# BattPower.net
KiCad netlist of a schematic drawn in Altium Designer
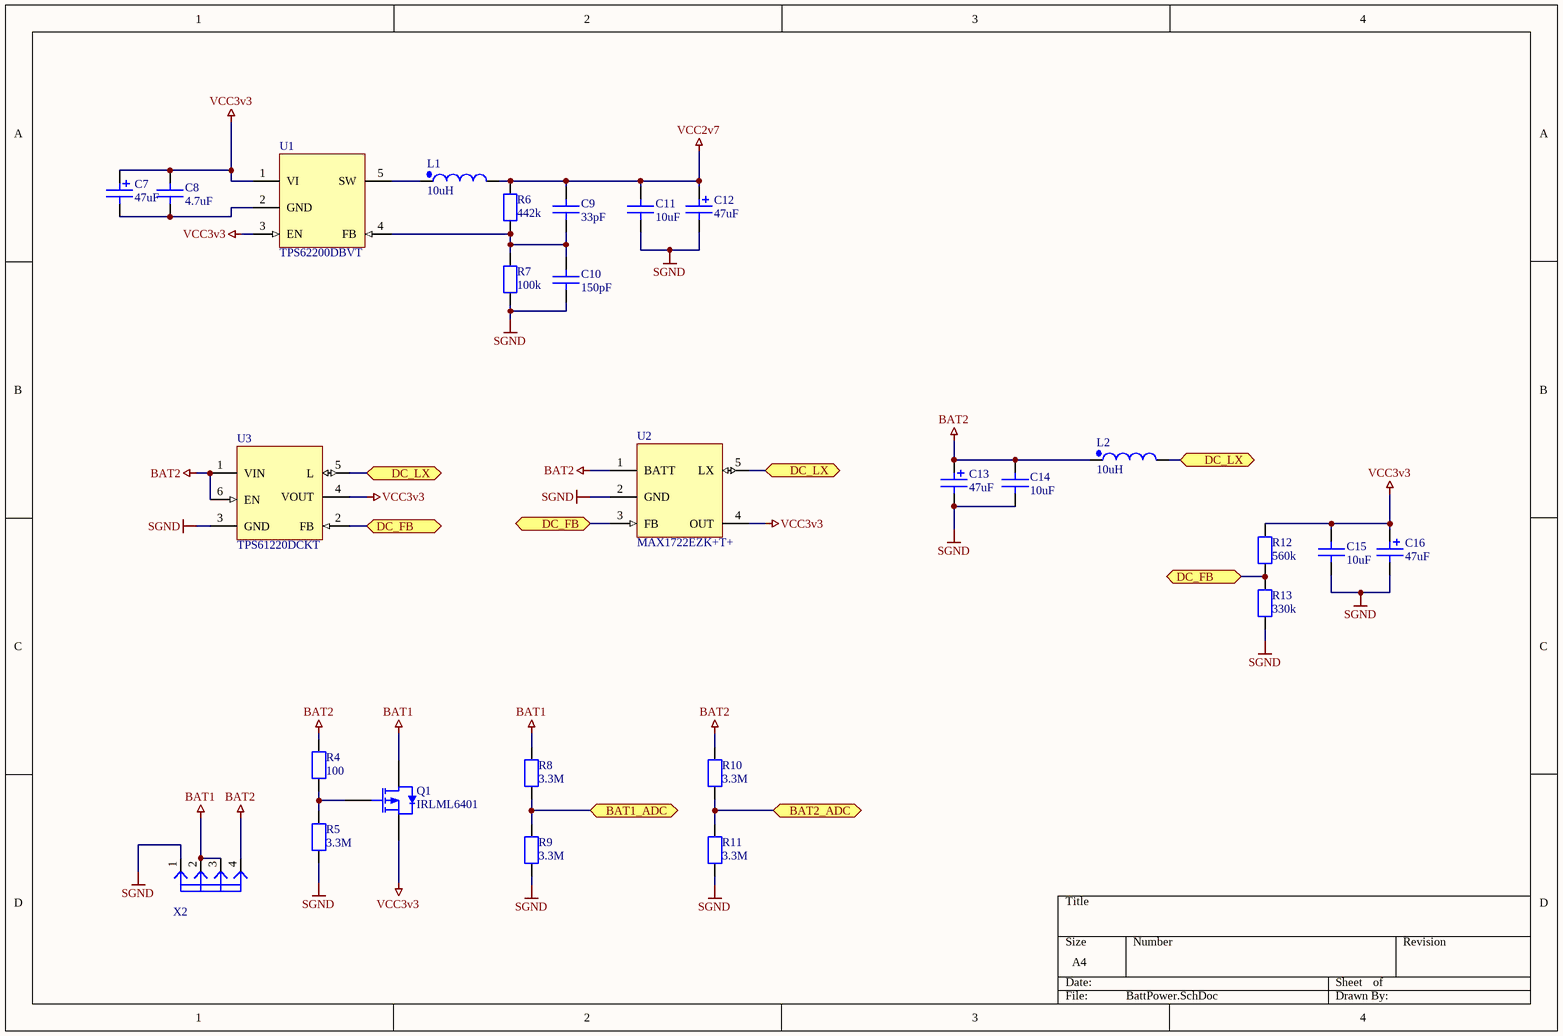
[diagram p0: BattPower.SchDoc]

(export (version "E")
  (design (tool "Eeschema 10.0.6"))
  (components
    (comp (ref "C7")
      (value "47uF")
      (footprint "TC2917")
      (description "C47uF-10V-tant")
      (fields (field (name "VOLTAGE") "10V"))
      (libsource (lib "MCounter_Common") (part "C47uF-10V-tant"))
    )
    (comp (ref "C8")
      (value "4.7uF")
      (footprint "C0805")
      (description "C4.7uF-16V")
      (fields (field (name "VOLTAGE") "16V"))
      (libsource (lib "MCounter_Common") (part "C4.7uF-16V"))
    )
    (comp (ref "C9")
      (value "33pF")
      (footprint "C0805")
      (description "C33pF-50V")
      (fields (field (name "VOLTAGE") "50V"))
      (libsource (lib "MCounter_Common") (part "C33pF-50V"))
    )
    (comp (ref "C10")
      (value "150pF")
      (footprint "C0805")
      (description "C150pF-50V")
      (fields (field (name "VOLTAGE") "50V"))
      (libsource (lib "MCounter_Common") (part "C150pF-50V"))
    )
    (comp (ref "C11")
      (value "10uF")
      (footprint "C0805")
      (description "C10uF-16V")
      (fields (field (name "VOLTAGE") "16V"))
      (libsource (lib "MCounter_Common") (part "C10uF-16V"))
    )
    (comp (ref "C12")
      (value "47uF")
      (footprint "TC2917")
      (description "C47uF-10V-tant")
      (fields (field (name "VOLTAGE") "10V"))
      (libsource (lib "MCounter_Common") (part "C47uF-10V-tant"))
    )
    (comp (ref "C13")
      (value "47uF")
      (footprint "TC2917")
      (description "C47uF-10V-tant")
      (fields (field (name "VOLTAGE") "10V"))
      (libsource (lib "MCounter_Common") (part "C47uF-10V-tant"))
    )
    (comp (ref "C14")
      (value "10uF")
      (footprint "C0805")
      (description "C10uF-16V")
      (fields (field (name "VOLTAGE") "16V"))
      (libsource (lib "MCounter_Common") (part "C10uF-16V"))
    )
    (comp (ref "C15")
      (value "10uF")
      (footprint "C0805")
      (description "C10uF-16V")
      (fields (field (name "VOLTAGE") "16V"))
      (libsource (lib "MCounter_Common") (part "C10uF-16V"))
    )
    (comp (ref "C16")
      (value "47uF")
      (footprint "TC2917")
      (description "C47uF-10V-tant")
      (fields (field (name "VOLTAGE") "10V"))
      (libsource (lib "MCounter_Common") (part "C47uF-10V-tant"))
    )
    (comp (ref "L1")
      (value "10uH")
      (footprint "CD54-CDRH4D")
      (description "Inductor with Winding Polarity Marking")
      (fields (field (name "Comment") "CD54"))
      (libsource (lib "MCounter_Common") (part "CD54NP-100M"))
    )
    (comp (ref "L2")
      (value "10uH")
      (footprint "CD54-CDRH4D")
      (description "Inductor with Winding Polarity Marking")
      (fields (field (name "Comment") "CD54"))
      (libsource (lib "MCounter_Common") (part "CD54NP-100M"))
    )
    (comp (ref "Q1")
      (value "IRLML6401")
      (footprint "SOT23_N")
      (description "P-Channel Power MOSFET")
      (libsource (lib "MCounter_Common") (part "IRLML6401"))
    )
    (comp (ref "R4")
      (value "100")
      (footprint "R0805")
      (description "R-100-5%")
      (fields (field (name "Comment") "R100-5%"))
      (libsource (lib "MCounter_Common") (part "R100-5%"))
    )
    (comp (ref "R5")
      (value "3.3M")
      (footprint "R0805")
      (description "R3.3M-5%")
      (libsource (lib "MCounter_Common") (part "R3.3M-5%"))
    )
    (comp (ref "R6")
      (value "442k")
      (footprint "R0805")
      (description "R442k-1%")
      (libsource (lib "MCounter_Common") (part "R442k-1%"))
    )
    (comp (ref "R7")
      (value "100k")
      (footprint "R0805")
      (description "R100k-1%")
      (libsource (lib "MCounter_Common") (part "R100k-1%"))
    )
    (comp (ref "R8")
      (value "3.3M")
      (footprint "R0805")
      (description "R3.3M-5%")
      (libsource (lib "MCounter_Common") (part "R3.3M-5%"))
    )
    (comp (ref "R9")
      (value "3.3M")
      (footprint "R0805")
      (description "R3.3M-5%")
      (libsource (lib "MCounter_Common") (part "R3.3M-5%"))
    )
    (comp (ref "R10")
      (value "3.3M")
      (footprint "R0805")
      (description "R3.3M-5%")
      (libsource (lib "MCounter_Common") (part "R3.3M-5%"))
    )
    (comp (ref "R11")
      (value "3.3M")
      (footprint "R0805")
      (description "R3.3M-5%")
      (libsource (lib "MCounter_Common") (part "R3.3M-5%"))
    )
    (comp (ref "R12")
      (value "560k")
      (footprint "R0805")
      (description "R560k-1%")
      (libsource (lib "MCounter_Common") (part "R560k-1%"))
    )
    (comp (ref "R13")
      (value "330k")
      (footprint "R0805")
      (description "R330k-1%")
      (libsource (lib "MCounter_Common") (part "R330k-1%"))
    )
    (comp (ref "U1")
      (value "TPS62200DBVT")
      (footprint "5ST1_N")
      (description "High efficiency step-down DC-DC convertor, 5-pin SOT23")
      (libsource (lib "MCounter_Common") (part "TPS62200DBVT"))
    )
    (comp (ref "U2")
      (value "MAX1722EZK+T+")
      (footprint "5ST1_N")
      (description "High efficiency step-down DC-DC convertor, 5-pin SOT23")
      (libsource (lib "MCounter_Common") (part "MAX1722EZK+T+"))
    )
    (comp (ref "U3")
      (value "TPS61220DCKT")
      (footprint "SC70-6-N")
      (description "Low input voltage step-up DC-DC convertor, 6-pin SC70")
      (libsource (lib "MCounter_Common") (part "TPS61220DCKT"))
    )
    (comp (ref "X2") (value "PLS-4") (footprint "PLS-4") (libsource (lib "MCounter_Common") (part "PLS-4")))
  )
  (nets
    (net (code "1") (name "/BAT1_ADC") (class "Default")
      (node (ref "R8") (pin "1") (pinfunction "1_1") (pintype "passive"))
      (node (ref "R9") (pin "2") (pinfunction "2_2") (pintype "passive"))
    )
    (net (code "2") (name "/BAT2_ADC") (class "Default")
      (node (ref "R10") (pin "1") (pinfunction "1_1") (pintype "passive"))
      (node (ref "R11") (pin "2") (pinfunction "2_2") (pintype "passive"))
    )
    (net (code "3") (name "/DC_FB") (class "Default")
      (node (ref "R12") (pin "1") (pinfunction "1_1") (pintype "passive"))
      (node (ref "R13") (pin "2") (pinfunction "2_2") (pintype "passive"))
      (node (ref "U2") (pin "3") (pinfunction "FB_3") (pintype "input"))
      (node (ref "U3") (pin "2") (pinfunction "FB_2") (pintype "input"))
    )
    (net (code "4") (name "/DC_LX") (class "Default")
      (node (ref "L2") (pin "2") (pinfunction "2_2") (pintype "passive"))
      (node (ref "U2") (pin "5") (pinfunction "LX_5") (pintype "bidirectional"))
      (node (ref "U3") (pin "5") (pinfunction "L_5") (pintype "bidirectional"))
    )
    (net (code "5") (name "BAT1") (class "Default")
      (node (ref "Q1") (pin "3") (pinfunction "D_3") (pintype "passive"))
      (node (ref "R8") (pin "2") (pinfunction "2_2") (pintype "passive"))
      (node (ref "X2") (pin "2") (pinfunction "2_2") (pintype "passive"))
      (node (ref "X2") (pin "3") (pinfunction "3_3") (pintype "passive"))
    )
    (net (code "6") (name "BAT2") (class "Default")
      (node (ref "C13") (pin "1") (pinfunction "1_1") (pintype "passive"))
      (node (ref "C14") (pin "2") (pinfunction "2_2") (pintype "passive"))
      (node (ref "L2") (pin "1") (pinfunction "1_1") (pintype "passive"))
      (node (ref "R10") (pin "2") (pinfunction "2_2") (pintype "passive"))
      (node (ref "R4") (pin "2") (pinfunction "2_2") (pintype "passive"))
      (node (ref "U2") (pin "1") (pinfunction "BATT_1") (pintype "power_in"))
      (node (ref "U3") (pin "1") (pinfunction "VIN_1") (pintype "power_in"))
      (node (ref "U3") (pin "6") (pinfunction "EN_6") (pintype "input"))
      (node (ref "X2") (pin "4") (pinfunction "4_4") (pintype "passive"))
    )
    (net (code "7") (name "Net-(Q1-G)") (class "Default")
      (node (ref "Q1") (pin "1") (pinfunction "G_1") (pintype "passive"))
      (node (ref "R4") (pin "1") (pinfunction "1_1") (pintype "passive"))
      (node (ref "R5") (pin "2") (pinfunction "2_2") (pintype "passive"))
    )
    (net (code "8") (name "Net-(U1-FB)") (class "Default")
      (node (ref "C10") (pin "2") (pinfunction "2_2") (pintype "passive"))
      (node (ref "C9") (pin "1") (pinfunction "1_1") (pintype "passive"))
      (node (ref "R6") (pin "1") (pinfunction "1_1") (pintype "passive"))
      (node (ref "R7") (pin "2") (pinfunction "2_2") (pintype "passive"))
      (node (ref "U1") (pin "4") (pinfunction "FB_4") (pintype "input"))
    )
    (net (code "9") (name "Net-(U1-GND)") (class "Default")
      (node (ref "C7") (pin "2") (pinfunction "2_2") (pintype "passive"))
      (node (ref "C8") (pin "1") (pinfunction "1_1") (pintype "passive"))
      (node (ref "U1") (pin "2") (pinfunction "GND_2") (pintype "power_in"))
    )
    (net (code "10") (name "Net-(U1-SW)") (class "Default")
      (node (ref "L1") (pin "1") (pinfunction "1_1") (pintype "passive"))
      (node (ref "U1") (pin "5") (pinfunction "SW_5") (pintype "power_in"))
    )
    (net (code "11") (name "SGND") (class "Default")
      (node (ref "C10") (pin "1") (pinfunction "1_1") (pintype "passive"))
      (node (ref "C11") (pin "1") (pinfunction "1_1") (pintype "passive"))
      (node (ref "C12") (pin "2") (pinfunction "2_2") (pintype "passive"))
      (node (ref "C13") (pin "2") (pinfunction "2_2") (pintype "passive"))
      (node (ref "C14") (pin "1") (pinfunction "1_1") (pintype "passive"))
      (node (ref "C15") (pin "1") (pinfunction "1_1") (pintype "passive"))
      (node (ref "C16") (pin "2") (pinfunction "2_2") (pintype "passive"))
      (node (ref "R11") (pin "1") (pinfunction "1_1") (pintype "passive"))
      (node (ref "R13") (pin "1") (pinfunction "1_1") (pintype "passive"))
      (node (ref "R5") (pin "1") (pinfunction "1_1") (pintype "passive"))
      (node (ref "R7") (pin "1") (pinfunction "1_1") (pintype "passive"))
      (node (ref "R9") (pin "1") (pinfunction "1_1") (pintype "passive"))
      (node (ref "U2") (pin "2") (pinfunction "GND_2") (pintype "power_in"))
      (node (ref "U3") (pin "3") (pinfunction "GND_3") (pintype "power_in"))
      (node (ref "X2") (pin "1") (pinfunction "1_1") (pintype "passive"))
    )
    (net (code "12") (name "VCC2v7") (class "Default")
      (node (ref "C11") (pin "2") (pinfunction "2_2") (pintype "passive"))
      (node (ref "C12") (pin "1") (pinfunction "1_1") (pintype "passive"))
      (node (ref "C9") (pin "2") (pinfunction "2_2") (pintype "passive"))
      (node (ref "L1") (pin "2") (pinfunction "2_2") (pintype "passive"))
      (node (ref "R6") (pin "2") (pinfunction "2_2") (pintype "passive"))
    )
    (net (code "13") (name "VCC3v3") (class "Default")
      (node (ref "C15") (pin "2") (pinfunction "2_2") (pintype "passive"))
      (node (ref "C16") (pin "1") (pinfunction "1_1") (pintype "passive"))
      (node (ref "C7") (pin "1") (pinfunction "1_1") (pintype "passive"))
      (node (ref "C8") (pin "2") (pinfunction "2_2") (pintype "passive"))
      (node (ref "Q1") (pin "2") (pinfunction "S_2") (pintype "passive"))
      (node (ref "R12") (pin "2") (pinfunction "2_2") (pintype "passive"))
      (node (ref "U1") (pin "1") (pinfunction "VI_1") (pintype "power_in"))
      (node (ref "U1") (pin "3") (pinfunction "EN_3") (pintype "input"))
      (node (ref "U2") (pin "4") (pinfunction "OUT_4") (pintype "power_in"))
      (node (ref "U3") (pin "4") (pinfunction "VOUT_4") (pintype "power_in"))
    )
  )
)
